# Power.net
KiCad netlist of a schematic drawn in Altium Designer
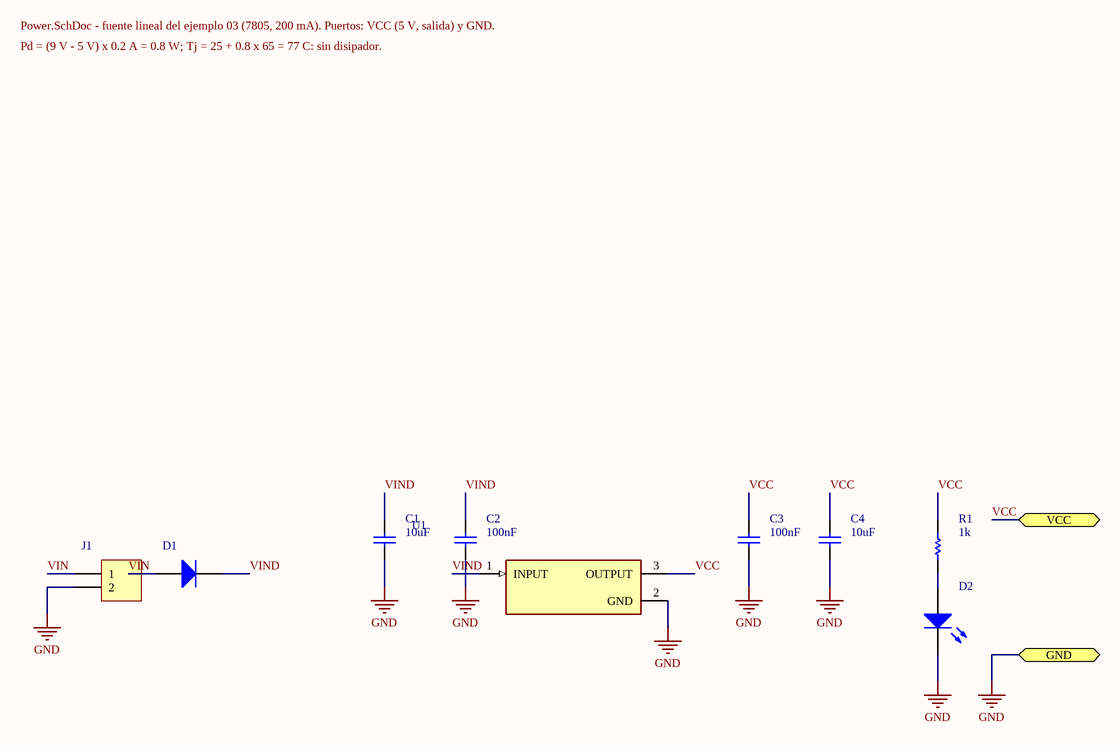
[diagram p0: Power.SchDoc]

(export (version "E")
  (design (tool "Eeschema 10.0.6"))
  (components
    (comp (ref "C1")
      (value "10uF")
      (description "Capacitor 10 uF (entrada)")
      (fields
        (field (name "MANUFACTURER") "KEMET")
        (field (name "MANUFACTURER PART NUMBER") "C320C106K3R5TA")
        (field (name "PUBLISHER") "Altium Limited")
      )
      (libsource (lib "Miscellaneous Devices") (part "Cap"))
    )
    (comp (ref "C2")
      (value "100nF")
      (description "Capacitor 100 nF (entrada)")
      (fields
        (field (name "MANUFACTURER") "KEMET")
        (field (name "MANUFACTURER PART NUMBER") "C320C104K5R5TA")
        (field (name "PUBLISHER") "Altium Limited")
      )
      (libsource (lib "Miscellaneous Devices") (part "Cap"))
    )
    (comp (ref "C3")
      (value "100nF")
      (description "Capacitor 100 nF (salida)")
      (fields
        (field (name "MANUFACTURER") "KEMET")
        (field (name "MANUFACTURER PART NUMBER") "C320C104K5R5TA")
        (field (name "PUBLISHER") "Altium Limited")
      )
      (libsource (lib "Miscellaneous Devices") (part "Cap"))
    )
    (comp (ref "C4")
      (value "10uF")
      (description "Capacitor 10 uF (salida)")
      (fields
        (field (name "MANUFACTURER") "KEMET")
        (field (name "MANUFACTURER PART NUMBER") "C320C106K3R5TA")
        (field (name "PUBLISHER") "Altium Limited")
      )
      (libsource (lib "Miscellaneous Devices") (part "Cap"))
    )
    (comp (ref "D1")
      (value "Diode 1N4007")
      (description "Diodo de proteccion de polaridad inversa")
      (fields
        (field (name "MANUFACTURER") "Diodes Inc.")
        (field (name "MANUFACTURER PART NUMBER") "1N4007")
        (field (name "PUBLISHER") "Altium Limited")
      )
      (libsource (lib "Miscellaneous Devices") (part "Diode 1N4007"))
    )
    (comp (ref "D2")
      (value "LED1")
      (description "LED rojo 5 mm (encendido)")
      (fields
        (field (name "MANUFACTURER") "Kingbright")
        (field (name "MANUFACTURER PART NUMBER") "WP7113ID")
        (field (name "PUBLISHER") "Altium Limited")
      )
      (libsource (lib "Miscellaneous Devices") (part "LED1"))
    )
    (comp (ref "J1")
      (value "Header 2")
      (description "Header 2 pin: Vin (7-12 V) y GND")
      (fields
        (field (name "MANUFACTURER") "Generic")
        (field (name "MANUFACTURER PART NUMBER") "Pin header 1x2")
        (field (name "PUBLISHER") "Altium Limited")
      )
      (libsource (lib "Miscellaneous Connectors") (part "Header 2"))
    )
    (comp (ref "R1")
      (value "1k")
      (description "Resistor 1 kohm 1/4 W (LED)")
      (fields
        (field (name "MANUFACTURER") "Yageo")
        (field (name "MANUFACTURER PART NUMBER") "CFR-25JB-52-1K")
        (field (name "PUBLISHER") "Altium Limited")
      )
      (libsource (lib "Miscellaneous Devices") (part "Res1"))
    )
    (comp (ref "U1")
      (value "LM7805T")
      (footprint "TO254P1011X457X1950-3")
      (description "Regulador lineal fijo 5 V, 1.5 A, TO-220")
      (fields (field (name "MF") "TAEJIN") (field (name "MANUFACTURER") "STMicroelectronics"))
      (libsource (lib "LM7805T") (part "LM7805T"))
    )
  )
  (nets
    (net (code "1") (name "/VCC") (class "Default")
      (node (ref "C3") (pin "2") (pinfunction "2_2") (pintype "passive"))
      (node (ref "C4") (pin "2") (pinfunction "2_2") (pintype "passive"))
      (node (ref "R1") (pin "2") (pinfunction "2_2") (pintype "passive"))
      (node (ref "U1") (pin "3") (pinfunction "OUTPUT_3") (pintype "power_in"))
    )
    (net (code "2") (name "/VIN") (class "Default")
      (node (ref "D1") (pin "1") (pinfunction "A_1") (pintype "passive"))
      (node (ref "J1") (pin "1") (pinfunction "1_1") (pintype "passive"))
    )
    (net (code "3") (name "/VIND") (class "Default")
      (node (ref "C1") (pin "2") (pinfunction "2_2") (pintype "passive"))
      (node (ref "C2") (pin "2") (pinfunction "2_2") (pintype "passive"))
      (node (ref "D1") (pin "2") (pinfunction "K_2") (pintype "passive"))
      (node (ref "U1") (pin "1") (pinfunction "INPUT_1") (pintype "input"))
    )
    (net (code "4") (name "GND") (class "Default")
      (node (ref "C1") (pin "1") (pinfunction "1_1") (pintype "passive"))
      (node (ref "C2") (pin "1") (pinfunction "1_1") (pintype "passive"))
      (node (ref "C3") (pin "1") (pinfunction "1_1") (pintype "passive"))
      (node (ref "C4") (pin "1") (pinfunction "1_1") (pintype "passive"))
      (node (ref "D2") (pin "2") (pinfunction "K_2") (pintype "passive"))
      (node (ref "J1") (pin "2") (pinfunction "2_2") (pintype "passive"))
      (node (ref "U1") (pin "2") (pinfunction "GND_2") (pintype "power_in"))
    )
    (net (code "5") (name "Net-(D2-A)") (class "Default")
      (node (ref "D2") (pin "1") (pinfunction "A_1") (pintype "passive"))
      (node (ref "R1") (pin "1") (pinfunction "1_1") (pintype "passive"))
    )
  )
)
